# Sheet2.net
KiCad netlist of a schematic drawn in Altium Designer
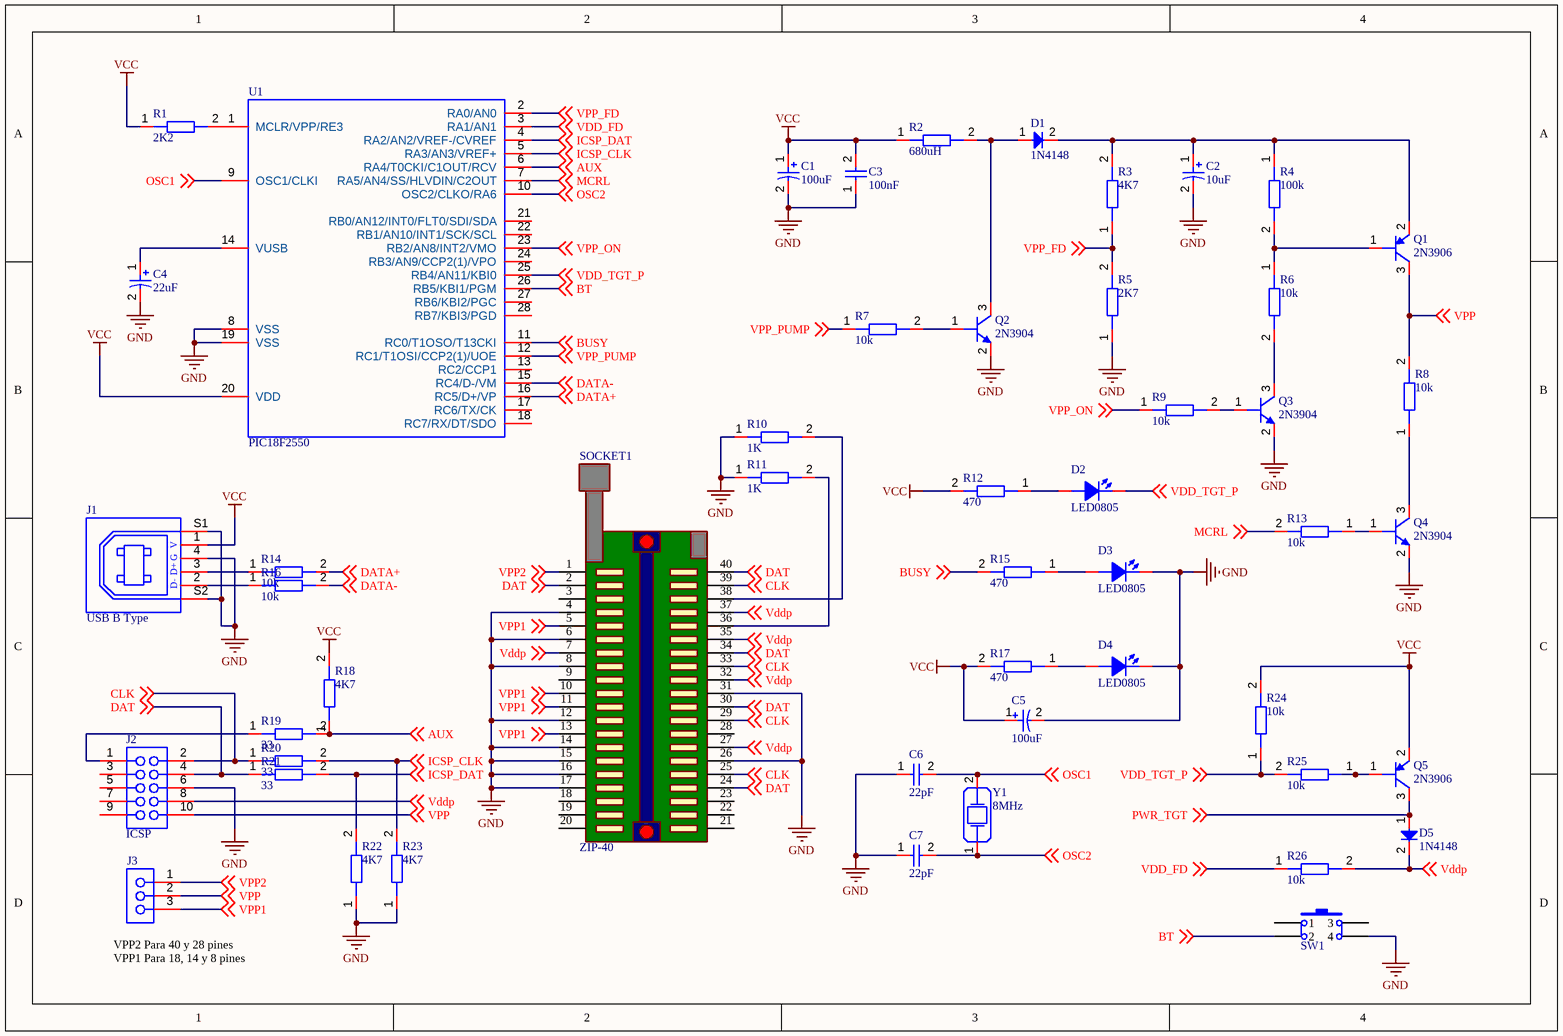
[diagram p0: Sheet2.SchDoc]

(export (version "E")
  (design (tool "Eeschema 10.0.6"))
  (components
    (comp (ref "C1")
      (value "100uF")
      (footprint "CAP_6.3_100uF")
      (libsource (lib "SMDLibrary") (part "Capacitor(Radian)"))
    )
    (comp (ref "C2")
      (value "10uF")
      (footprint "CAP_6.3_100uF")
      (libsource (lib "SMDLibrary") (part "Capacitor(Radian)"))
    )
    (comp (ref "C3")
      (value "100nF")
      (footprint "C0805")
      (libsource (lib "SMDLibrary") (part "Capacitors(SMD)"))
    )
    (comp (ref "C4")
      (value "22uF")
      (footprint "CAP_6.3_100uF")
      (libsource (lib "SMDLibrary") (part "Capacitor(Radian)"))
    )
    (comp (ref "C5")
      (value "100uF")
      (footprint "CAP_6.3_100uF")
      (libsource (lib "SMDLibrary") (part "Capacitor(Radian)"))
    )
    (comp (ref "C6")
      (value "22pF")
      (footprint "C0805")
      (libsource (lib "SMDLibrary") (part "Capacitors(SMD)"))
    )
    (comp (ref "C7")
      (value "22pF")
      (footprint "C0805")
      (libsource (lib "SMDLibrary") (part "Capacitors(SMD)"))
    )
    (comp (ref "D1")
      (value "1N4148")
      (footprint "DO-213AB")
      (libsource (lib "SMDLibrary") (part "Diode 1N4148 SMD"))
    )
    (comp (ref "D2") (value "LED0805") (footprint "L0805RED") (libsource (lib "SMDLibrary") (part "LED0805")))
    (comp (ref "D3") (value "LED0805") (footprint "L0805RED") (libsource (lib "SMDLibrary") (part "LED0805")))
    (comp (ref "D4") (value "LED0805") (footprint "L0805RED") (libsource (lib "SMDLibrary") (part "LED0805")))
    (comp (ref "D5")
      (value "1N4148")
      (footprint "DO-213AB")
      (libsource (lib "SMDLibrary") (part "Diode 1N4148 SMD"))
    )
    (comp (ref "J1")
      (value "USB B Type")
      (footprint "USB-B-TYPE")
      (libsource (lib "SMDLibrary") (part "USB B Type"))
    )
    (comp (ref "J2")
      (value "ICSP")
      (footprint "IDC_CONNECTOR_10x2.54")
      (libsource (lib "SMDLibrary") (part "IDC_CONNECTOR_5x2"))
    )
    (comp (ref "J3")
      (value "Header 3x1 TH Pitch 2.54mm")
      (footprint "Header 3x1 TH Pitch 2.54mm")
      (libsource (lib "SMDLibrary") (part "Header 3x1 TH Pitch 2.54mm"))
    )
    (comp (ref "Q1") (value "2N3906") (footprint "SOT23-3") (libsource (lib "SMDLibrary") (part "2N3906")))
    (comp (ref "Q2") (value "2N3904") (footprint "SOT23-3") (libsource (lib "SMDLibrary") (part "2N3904")))
    (comp (ref "Q3") (value "2N3904") (footprint "SOT23-3") (libsource (lib "SMDLibrary") (part "2N3904")))
    (comp (ref "Q4") (value "2N3904") (footprint "SOT23-3") (libsource (lib "SMDLibrary") (part "2N3904")))
    (comp (ref "Q5") (value "2N3906") (footprint "SOT23-3") (libsource (lib "SMDLibrary") (part "2N3906")))
    (comp (ref "R1") (value "2K2") (footprint "R0805") (libsource (lib "") (part "Resistor SMD_1")))
    (comp (ref "R2")
      (value "680uH")
      (footprint "RES-0.5W-HH-MO")
      (libsource (lib "SMDLibrary") (part "Resistors THD"))
    )
    (comp (ref "R3") (value "4K7") (footprint "R0805") (libsource (lib "") (part "Resistor SMD_3")))
    (comp (ref "R4") (value "100k") (footprint "R0805") (libsource (lib "") (part "Resistor SMD_2")))
    (comp (ref "R5") (value "2K7") (footprint "R0805") (libsource (lib "") (part "Resistor SMD_3")))
    (comp (ref "R6") (value "10k") (footprint "R0805") (libsource (lib "") (part "Resistor SMD_2")))
    (comp (ref "R7") (value "10k") (footprint "R0805") (libsource (lib "") (part "Resistor SMD_1")))
    (comp (ref "R8") (value "10k") (footprint "R0805") (libsource (lib "") (part "Resistor SMD_3")))
    (comp (ref "R9") (value "10k") (footprint "R0805") (libsource (lib "") (part "Resistor SMD_1")))
    (comp (ref "R10") (value "1K") (footprint "R0805") (libsource (lib "") (part "Resistor SMD_1")))
    (comp (ref "R11") (value "1K") (footprint "R0805") (libsource (lib "") (part "Resistor SMD_1")))
    (comp (ref "R12") (value "470") (footprint "R0805") (libsource (lib "SMDLibrary") (part "Resistor SMD")))
    (comp (ref "R13") (value "10k") (footprint "R0805") (libsource (lib "SMDLibrary") (part "Resistor SMD")))
    (comp (ref "R14") (value "10k") (footprint "R0805") (libsource (lib "") (part "Resistor SMD_1")))
    (comp (ref "R15") (value "470") (footprint "R0805") (libsource (lib "SMDLibrary") (part "Resistor SMD")))
    (comp (ref "R16") (value "10k") (footprint "R0805") (libsource (lib "") (part "Resistor SMD_1")))
    (comp (ref "R17") (value "470") (footprint "R0805") (libsource (lib "SMDLibrary") (part "Resistor SMD")))
    (comp (ref "R18") (value "4K7") (footprint "R0805") (libsource (lib "") (part "Resistor SMD_3")))
    (comp (ref "R19") (value "33") (footprint "R0805") (libsource (lib "") (part "Resistor SMD_1")))
    (comp (ref "R20") (value "33") (footprint "R0805") (libsource (lib "") (part "Resistor SMD_1")))
    (comp (ref "R21") (value "33") (footprint "R0805") (libsource (lib "") (part "Resistor SMD_1")))
    (comp (ref "R22") (value "4K7") (footprint "R0805") (libsource (lib "") (part "Resistor SMD_3")))
    (comp (ref "R23") (value "4K7") (footprint "R0805") (libsource (lib "") (part "Resistor SMD_3")))
    (comp (ref "R24") (value "10k") (footprint "R0805") (libsource (lib "") (part "Resistor SMD_3")))
    (comp (ref "R25") (value "10k") (footprint "R0805") (libsource (lib "SMDLibrary") (part "Resistor SMD")))
    (comp (ref "R26") (value "10k") (footprint "R0805") (libsource (lib "") (part "Resistor SMD_1")))
    (comp (ref "SOCKET1")
      (value "ZIP-40")
      (footprint "ZIP-40")
      (libsource (lib "SMDLibrary") (part "ZIP-40"))
    )
    (comp (ref "SW1")
      (value "Button1")
      (footprint "BUTTON_HOLE_4.3mm")
      (libsource (lib "SMDLibrary") (part "Button1"))
    )
    (comp (ref "U1")
      (value "PIC18F2550")
      (footprint "DIP28_M04")
      (libsource (lib "SMDLibrary") (part "PIC18F2550"))
    )
    (comp (ref "Y1")
      (value "8MHz")
      (footprint "HC-49_THROUGH")
      (libsource (lib "SMDLibrary") (part "Crystal"))
    )
  )
  (nets
    (net (code "1") (name "AUX") (class "Default")
      (node (ref "R18") (pin "1") (pinfunction "1_1") (pintype "passive"))
      (node (ref "R19") (pin "2") (pinfunction "2_2") (pintype "passive"))
      (node (ref "U1") (pin "6") (pinfunction "RA4/T0CKI/C1OUT/RCV_6") (pintype "passive"))
    )
    (net (code "2") (name "BT") (class "Default")
      (node (ref "SW1") (pin "2") (pinfunction "2_2") (pintype "passive"))
      (node (ref "U1") (pin "26") (pinfunction "RB5/KBI1/PGM_26") (pintype "passive"))
    )
    (net (code "3") (name "BUSY") (class "Default")
      (node (ref "R15") (pin "2") (pinfunction "2_2") (pintype "passive"))
      (node (ref "U1") (pin "11") (pinfunction "RC0/T1OSO/T13CKI_11") (pintype "passive"))
    )
    (net (code "4") (name "CLK") (class "Default")
      (node (ref "J2") (pin "2") (pinfunction "2_2") (pintype "passive"))
      (node (ref "R20") (pin "1") (pinfunction "1_1") (pintype "passive"))
      (node (ref "SOCKET1") (pin "25") (pinfunction "25_25") (pintype "passive"))
      (node (ref "SOCKET1") (pin "29") (pinfunction "29_29") (pintype "passive"))
      (node (ref "SOCKET1") (pin "33") (pinfunction "33_33") (pintype "passive"))
      (node (ref "SOCKET1") (pin "39") (pinfunction "39_39") (pintype "passive"))
    )
    (net (code "5") (name "DAT") (class "Default")
      (node (ref "J2") (pin "4") (pinfunction "4_4") (pintype "passive"))
      (node (ref "R21") (pin "1") (pinfunction "1_1") (pintype "passive"))
      (node (ref "SOCKET1") (pin "2") (pinfunction "2_2") (pintype "passive"))
      (node (ref "SOCKET1") (pin "24") (pinfunction "24_24") (pintype "passive"))
      (node (ref "SOCKET1") (pin "30") (pinfunction "30_30") (pintype "passive"))
      (node (ref "SOCKET1") (pin "34") (pinfunction "34_34") (pintype "passive"))
      (node (ref "SOCKET1") (pin "40") (pinfunction "40_40") (pintype "passive"))
    )
    (net (code "6") (name "DATA+") (class "Default")
      (node (ref "R14") (pin "2") (pinfunction "2_2") (pintype "passive"))
      (node (ref "U1") (pin "16") (pinfunction "RC5/D+/VP_16") (pintype "passive"))
    )
    (net (code "7") (name "DATA-") (class "Default")
      (node (ref "R16") (pin "2") (pinfunction "2_2") (pintype "passive"))
      (node (ref "U1") (pin "15") (pinfunction "RC4/D-/VM_15") (pintype "passive"))
    )
    (net (code "8") (name "GND") (class "Default")
      (node (ref "C1") (pin "2") (pinfunction "2_2") (pintype "passive"))
      (node (ref "C2") (pin "2") (pinfunction "2_2") (pintype "passive"))
      (node (ref "C3") (pin "1") (pinfunction "1_1") (pintype "passive"))
      (node (ref "C4") (pin "2") (pinfunction "2_2") (pintype "passive"))
      (node (ref "C5") (pin "2") (pinfunction "2_2") (pintype "passive"))
      (node (ref "C6") (pin "1") (pinfunction "1_1") (pintype "passive"))
      (node (ref "C7") (pin "1") (pinfunction "1_1") (pintype "passive"))
      (node (ref "D3") (pin "2") (pinfunction "K_2") (pintype "passive"))
      (node (ref "D4") (pin "2") (pinfunction "K_2") (pintype "passive"))
      (node (ref "J1") (pin "4") (pinfunction "4_4") (pintype "passive"))
      (node (ref "J1") (pin "S1") (pinfunction "S1_S1") (pintype "passive"))
      (node (ref "J1") (pin "S2") (pinfunction "S2_S2") (pintype "passive"))
      (node (ref "J2") (pin "6") (pinfunction "6_6") (pintype "passive"))
      (node (ref "Q2") (pin "2") (pinfunction "E_2") (pintype "passive"))
      (node (ref "Q3") (pin "2") (pinfunction "E_2") (pintype "passive"))
      (node (ref "Q4") (pin "2") (pinfunction "E_2") (pintype "passive"))
      (node (ref "R10") (pin "1") (pinfunction "1_1") (pintype "passive"))
      (node (ref "R11") (pin "1") (pinfunction "1_1") (pintype "passive"))
      (node (ref "R22") (pin "1") (pinfunction "1_1") (pintype "passive"))
      (node (ref "R23") (pin "1") (pinfunction "1_1") (pintype "passive"))
      (node (ref "R5") (pin "1") (pinfunction "1_1") (pintype "passive"))
      (node (ref "SOCKET1") (pin "12") (pinfunction "12_12") (pintype "passive"))
      (node (ref "SOCKET1") (pin "14") (pinfunction "14_14") (pintype "passive"))
      (node (ref "SOCKET1") (pin "15") (pinfunction "15_15") (pintype "passive"))
      (node (ref "SOCKET1") (pin "16") (pinfunction "16_16") (pintype "passive"))
      (node (ref "SOCKET1") (pin "17") (pinfunction "17_17") (pintype "passive"))
      (node (ref "SOCKET1") (pin "26") (pinfunction "26_26") (pintype "passive"))
      (node (ref "SOCKET1") (pin "31") (pinfunction "31_31") (pintype "passive"))
      (node (ref "SOCKET1") (pin "4") (pinfunction "4_4") (pintype "passive"))
      (node (ref "SOCKET1") (pin "6") (pinfunction "6_6") (pintype "passive"))
      (node (ref "SOCKET1") (pin "8") (pinfunction "8_8") (pintype "passive"))
      (node (ref "SW1") (pin "4") (pinfunction "4_4") (pintype "passive"))
      (node (ref "U1") (pin "19") (pinfunction "VSS_19") (pintype "passive"))
      (node (ref "U1") (pin "8") (pinfunction "VSS_8") (pintype "passive"))
    )
    (net (code "9") (name "ICSP_CLK") (class "Default")
      (node (ref "R20") (pin "2") (pinfunction "2_2") (pintype "passive"))
      (node (ref "R23") (pin "2") (pinfunction "2_2") (pintype "passive"))
      (node (ref "U1") (pin "5") (pinfunction "RA3/AN3/VREF+_5") (pintype "passive"))
    )
    (net (code "10") (name "ICSP_DAT") (class "Default")
      (node (ref "R21") (pin "2") (pinfunction "2_2") (pintype "passive"))
      (node (ref "R22") (pin "2") (pinfunction "2_2") (pintype "passive"))
      (node (ref "U1") (pin "4") (pinfunction "RA2/AN2/VREF-/CVREF_4") (pintype "passive"))
    )
    (net (code "11") (name "MCRL") (class "Default")
      (node (ref "R13") (pin "2") (pinfunction "2_2") (pintype "passive"))
      (node (ref "U1") (pin "7") (pinfunction "RA5/AN4/SS/HLVDIN/C2OUT_7") (pintype "passive"))
    )
    (net (code "12") (name "Net-(D2-A)") (class "Default")
      (node (ref "D2") (pin "1") (pinfunction "A_1") (pintype "passive"))
      (node (ref "R12") (pin "1") (pinfunction "1_1") (pintype "passive"))
    )
    (net (code "13") (name "Net-(D3-A)") (class "Default")
      (node (ref "D3") (pin "1") (pinfunction "A_1") (pintype "passive"))
      (node (ref "R15") (pin "1") (pinfunction "1_1") (pintype "passive"))
    )
    (net (code "14") (name "Net-(D4-A)") (class "Default")
      (node (ref "D4") (pin "1") (pinfunction "A_1") (pintype "passive"))
      (node (ref "R17") (pin "1") (pinfunction "1_1") (pintype "passive"))
    )
    (net (code "15") (name "Net-(J1-Pad2)") (class "Default")
      (node (ref "J1") (pin "2") (pinfunction "2_2") (pintype "passive"))
      (node (ref "R16") (pin "1") (pinfunction "1_1") (pintype "passive"))
    )
    (net (code "16") (name "Net-(J1-Pad3)") (class "Default")
      (node (ref "J1") (pin "3") (pinfunction "3_3") (pintype "passive"))
      (node (ref "R14") (pin "1") (pinfunction "1_1") (pintype "passive"))
    )
    (net (code "17") (name "Net-(J2-Pad1)") (class "Default")
      (node (ref "J2") (pin "1") (pinfunction "1_1") (pintype "passive"))
      (node (ref "R19") (pin "1") (pinfunction "1_1") (pintype "passive"))
    )
    (net (code "18") (name "Net-(Q1-B)") (class "Default")
      (node (ref "Q1") (pin "1") (pinfunction "B_1") (pintype "passive"))
      (node (ref "R4") (pin "2") (pinfunction "2_2") (pintype "passive"))
      (node (ref "R6") (pin "1") (pinfunction "1_1") (pintype "passive"))
    )
    (net (code "19") (name "Net-(Q1-E)") (class "Default")
      (node (ref "C2") (pin "1") (pinfunction "1_1") (pintype "passive"))
      (node (ref "D1") (pin "2") (pinfunction "2_2") (pintype "passive"))
      (node (ref "Q1") (pin "2") (pinfunction "E_2") (pintype "passive"))
      (node (ref "R3") (pin "2") (pinfunction "2_2") (pintype "passive"))
      (node (ref "R4") (pin "1") (pinfunction "1_1") (pintype "passive"))
    )
    (net (code "20") (name "Net-(Q2-B)") (class "Default")
      (node (ref "Q2") (pin "1") (pinfunction "B_1") (pintype "passive"))
      (node (ref "R7") (pin "2") (pinfunction "2_2") (pintype "passive"))
    )
    (net (code "21") (name "Net-(Q2-C)") (class "Default")
      (node (ref "D1") (pin "1") (pinfunction "1_1") (pintype "passive"))
      (node (ref "Q2") (pin "3") (pinfunction "C_3") (pintype "passive"))
      (node (ref "R2") (pin "2") (pinfunction "2_2") (pintype "passive"))
    )
    (net (code "22") (name "Net-(Q3-B)") (class "Default")
      (node (ref "Q3") (pin "1") (pinfunction "B_1") (pintype "passive"))
      (node (ref "R9") (pin "2") (pinfunction "2_2") (pintype "passive"))
    )
    (net (code "23") (name "Net-(Q3-C)") (class "Default")
      (node (ref "Q3") (pin "3") (pinfunction "C_3") (pintype "passive"))
      (node (ref "R6") (pin "2") (pinfunction "2_2") (pintype "passive"))
    )
    (net (code "24") (name "Net-(Q4-B)") (class "Default")
      (node (ref "Q4") (pin "1") (pinfunction "B_1") (pintype "passive"))
      (node (ref "R13") (pin "1") (pinfunction "1_1") (pintype "passive"))
    )
    (net (code "25") (name "Net-(Q4-C)") (class "Default")
      (node (ref "Q4") (pin "3") (pinfunction "C_3") (pintype "passive"))
      (node (ref "R8") (pin "1") (pinfunction "1_1") (pintype "passive"))
    )
    (net (code "26") (name "Net-(Q5-B)") (class "Default")
      (node (ref "Q5") (pin "1") (pinfunction "B_1") (pintype "passive"))
      (node (ref "R25") (pin "1") (pinfunction "1_1") (pintype "passive"))
    )
    (net (code "27") (name "Net-(R10-Pad2)") (class "Default")
      (node (ref "R10") (pin "2") (pinfunction "2_2") (pintype "passive"))
      (node (ref "SOCKET1") (pin "38") (pinfunction "38_38") (pintype "passive"))
    )
    (net (code "28") (name "Net-(R11-Pad2)") (class "Default")
      (node (ref "R11") (pin "2") (pinfunction "2_2") (pintype "passive"))
      (node (ref "SOCKET1") (pin "36") (pinfunction "36_36") (pintype "passive"))
    )
    (net (code "29") (name "Net-(U1-MCLR{slash}VPP{slash}RE3)") (class "Default")
      (node (ref "R1") (pin "2") (pinfunction "2_2") (pintype "passive"))
      (node (ref "U1") (pin "1") (pinfunction "MCLR/VPP/RE3_1") (pintype "passive"))
    )
    (net (code "30") (name "Net-(U1-VUSB)") (class "Default")
      (node (ref "C4") (pin "1") (pinfunction "1_1") (pintype "passive"))
      (node (ref "U1") (pin "14") (pinfunction "VUSB_14") (pintype "passive"))
    )
    (net (code "31") (name "OSC1") (class "Default")
      (node (ref "C6") (pin "2") (pinfunction "2_2") (pintype "passive"))
      (node (ref "U1") (pin "9") (pinfunction "OSC1/CLKI_9") (pintype "passive"))
      (node (ref "Y1") (pin "2") (pinfunction "2_2") (pintype "passive"))
    )
    (net (code "32") (name "OSC2") (class "Default")
      (node (ref "C7") (pin "2") (pinfunction "2_2") (pintype "passive"))
      (node (ref "U1") (pin "10") (pinfunction "OSC2/CLKO/RA6_10") (pintype "passive"))
      (node (ref "Y1") (pin "1") (pinfunction "1_1") (pintype "passive"))
    )
    (net (code "33") (name "PWR_TGT") (class "Default")
      (node (ref "D5") (pin "1") (pinfunction "1_1") (pintype "passive"))
      (node (ref "Q5") (pin "3") (pinfunction "C_3") (pintype "passive"))
    )
    (net (code "34") (name "VCC") (class "Default")
      (node (ref "C1") (pin "1") (pinfunction "1_1") (pintype "passive"))
      (node (ref "C3") (pin "2") (pinfunction "2_2") (pintype "passive"))
      (node (ref "C5") (pin "1") (pinfunction "1_1") (pintype "passive"))
      (node (ref "J1") (pin "1") (pinfunction "1_1") (pintype "passive"))
      (node (ref "Q5") (pin "2") (pinfunction "E_2") (pintype "passive"))
      (node (ref "R1") (pin "1") (pinfunction "1_1") (pintype "passive"))
      (node (ref "R12") (pin "2") (pinfunction "2_2") (pintype "passive"))
      (node (ref "R17") (pin "2") (pinfunction "2_2") (pintype "passive"))
      (node (ref "R18") (pin "2") (pinfunction "2_2") (pintype "passive"))
      (node (ref "R2") (pin "1") (pinfunction "1_1") (pintype "passive"))
      (node (ref "R24") (pin "2") (pinfunction "2_2") (pintype "passive"))
      (node (ref "U1") (pin "20") (pinfunction "VDD_20") (pintype "passive"))
    )
    (net (code "35") (name "VDD_FD") (class "Default")
      (node (ref "R26") (pin "1") (pinfunction "1_1") (pintype "passive"))
      (node (ref "U1") (pin "3") (pinfunction "RA1/AN1_3") (pintype "passive"))
    )
    (net (code "36") (name "VDD_TGT_P") (class "Default")
      (node (ref "D2") (pin "2") (pinfunction "K_2") (pintype "passive"))
      (node (ref "R24") (pin "1") (pinfunction "1_1") (pintype "passive"))
      (node (ref "R25") (pin "2") (pinfunction "2_2") (pintype "passive"))
      (node (ref "U1") (pin "25") (pinfunction "RB4/AN11/KBI0_25") (pintype "passive"))
    )
    (net (code "37") (name "VPP") (class "Default")
      (node (ref "J2") (pin "10") (pinfunction "10_10") (pintype "passive"))
      (node (ref "J3") (pin "2") (pinfunction "2_2") (pintype "passive"))
      (node (ref "Q1") (pin "3") (pinfunction "C_3") (pintype "passive"))
      (node (ref "R8") (pin "2") (pinfunction "2_2") (pintype "passive"))
    )
    (net (code "38") (name "VPP1") (class "Default")
      (node (ref "J3") (pin "3") (pinfunction "3_3") (pintype "passive"))
      (node (ref "SOCKET1") (pin "10") (pinfunction "10_10") (pintype "passive"))
      (node (ref "SOCKET1") (pin "11") (pinfunction "11_11") (pintype "passive"))
      (node (ref "SOCKET1") (pin "13") (pinfunction "13_13") (pintype "passive"))
      (node (ref "SOCKET1") (pin "5") (pinfunction "5_5") (pintype "passive"))
    )
    (net (code "39") (name "VPP2") (class "Default")
      (node (ref "J3") (pin "1") (pinfunction "1_1") (pintype "passive"))
      (node (ref "SOCKET1") (pin "1") (pinfunction "1_1") (pintype "passive"))
    )
    (net (code "40") (name "VPP_FD") (class "Default")
      (node (ref "R3") (pin "1") (pinfunction "1_1") (pintype "passive"))
      (node (ref "R5") (pin "2") (pinfunction "2_2") (pintype "passive"))
      (node (ref "U1") (pin "2") (pinfunction "RA0/AN0_2") (pintype "passive"))
    )
    (net (code "41") (name "VPP_ON") (class "Default")
      (node (ref "R9") (pin "1") (pinfunction "1_1") (pintype "passive"))
      (node (ref "U1") (pin "23") (pinfunction "RB2/AN8/INT2/VMO_23") (pintype "passive"))
    )
    (net (code "42") (name "VPP_PUMP") (class "Default")
      (node (ref "R7") (pin "1") (pinfunction "1_1") (pintype "passive"))
      (node (ref "U1") (pin "12") (pinfunction "RC1/T1OSI/CCP2(1)/UOE_12") (pintype "passive"))
    )
    (net (code "43") (name "Vddp") (class "Default")
      (node (ref "D5") (pin "2") (pinfunction "2_2") (pintype "passive"))
      (node (ref "J2") (pin "8") (pinfunction "8_8") (pintype "passive"))
      (node (ref "R26") (pin "2") (pinfunction "2_2") (pintype "passive"))
      (node (ref "SOCKET1") (pin "27") (pinfunction "27_27") (pintype "passive"))
      (node (ref "SOCKET1") (pin "32") (pinfunction "32_32") (pintype "passive"))
      (node (ref "SOCKET1") (pin "35") (pinfunction "35_35") (pintype "passive"))
      (node (ref "SOCKET1") (pin "37") (pinfunction "37_37") (pintype "passive"))
      (node (ref "SOCKET1") (pin "7") (pinfunction "7_7") (pintype "passive"))
    )
    (net (code "44") (name "unconnected-(J2-Pad3)") (class "Default")
      (node (ref "J2") (pin "3") (pinfunction "3_3") (pintype "passive"))
    )
    (net (code "45") (name "unconnected-(J2-Pad5)") (class "Default")
      (node (ref "J2") (pin "5") (pinfunction "5_5") (pintype "passive"))
    )
    (net (code "46") (name "unconnected-(J2-Pad7)") (class "Default")
      (node (ref "J2") (pin "7") (pinfunction "7_7") (pintype "passive"))
    )
    (net (code "47") (name "unconnected-(J2-Pad9)") (class "Default")
      (node (ref "J2") (pin "9") (pinfunction "9_9") (pintype "passive"))
    )
    (net (code "48") (name "unconnected-(SOCKET1-Pad3)") (class "Default")
      (node (ref "SOCKET1") (pin "3") (pinfunction "3_3") (pintype "passive"))
    )
    (net (code "49") (name "unconnected-(SOCKET1-Pad9)") (class "Default")
      (node (ref "SOCKET1") (pin "9") (pinfunction "9_9") (pintype "passive"))
    )
    (net (code "50") (name "unconnected-(SOCKET1-Pad18)") (class "Default")
      (node (ref "SOCKET1") (pin "18") (pinfunction "18_18") (pintype "passive"))
    )
    (net (code "51") (name "unconnected-(SOCKET1-Pad19)") (class "Default")
      (node (ref "SOCKET1") (pin "19") (pinfunction "19_19") (pintype "passive"))
    )
    (net (code "52") (name "unconnected-(SOCKET1-Pad20)") (class "Default")
      (node (ref "SOCKET1") (pin "20") (pinfunction "20_20") (pintype "passive"))
    )
    (net (code "53") (name "unconnected-(SOCKET1-Pad21)") (class "Default")
      (node (ref "SOCKET1") (pin "21") (pinfunction "21_21") (pintype "passive"))
    )
    (net (code "54") (name "unconnected-(SOCKET1-Pad22)") (class "Default")
      (node (ref "SOCKET1") (pin "22") (pinfunction "22_22") (pintype "passive"))
    )
    (net (code "55") (name "unconnected-(SOCKET1-Pad23)") (class "Default")
      (node (ref "SOCKET1") (pin "23") (pinfunction "23_23") (pintype "passive"))
    )
    (net (code "56") (name "unconnected-(SOCKET1-Pad28)") (class "Default")
      (node (ref "SOCKET1") (pin "28") (pinfunction "28_28") (pintype "passive"))
    )
    (net (code "57") (name "unconnected-(SW1-Pad1)") (class "Default")
      (node (ref "SW1") (pin "1") (pinfunction "1_1") (pintype "passive"))
    )
    (net (code "58") (name "unconnected-(SW1-Pad3)") (class "Default")
      (node (ref "SW1") (pin "3") (pinfunction "3_3") (pintype "passive"))
    )
    (net (code "59") (name "unconnected-(U1-RB0{slash}AN12{slash}INT0{slash}FLT0{slash}SDI{slash}SDA-Pad21)") (class "Default")
      (node (ref "U1") (pin "21") (pinfunction "RB0/AN12/INT0/FLT0/SDI/SDA_21") (pintype "passive"))
    )
    (net (code "60") (name "unconnected-(U1-RB1{slash}AN10{slash}INT1{slash}SCK{slash}SCL-Pad22)") (class "Default")
      (node (ref "U1") (pin "22") (pinfunction "RB1/AN10/INT1/SCK/SCL_22") (pintype "passive"))
    )
    (net (code "61") (name "unconnected-(U1-RB3{slash}AN9{slash}CCP2(1){slash}VPO-Pad24)") (class "Default")
      (node (ref "U1") (pin "24") (pinfunction "RB3/AN9/CCP2(1)/VPO_24") (pintype "passive"))
    )
    (net (code "62") (name "unconnected-(U1-RB6{slash}KBI2{slash}PGC-Pad27)") (class "Default")
      (node (ref "U1") (pin "27") (pinfunction "RB6/KBI2/PGC_27") (pintype "passive"))
    )
    (net (code "63") (name "unconnected-(U1-RB7{slash}KBI3{slash}PGD-Pad28)") (class "Default")
      (node (ref "U1") (pin "28") (pinfunction "RB7/KBI3/PGD_28") (pintype "passive"))
    )
    (net (code "64") (name "unconnected-(U1-RC2{slash}CCP1-Pad13)") (class "Default")
      (node (ref "U1") (pin "13") (pinfunction "RC2/CCP1_13") (pintype "passive"))
    )
    (net (code "65") (name "unconnected-(U1-RC6{slash}TX{slash}CK-Pad17)") (class "Default")
      (node (ref "U1") (pin "17") (pinfunction "RC6/TX/CK_17") (pintype "passive"))
    )
    (net (code "66") (name "unconnected-(U1-RC7{slash}RX{slash}DT{slash}SDO-Pad18)") (class "Default")
      (node (ref "U1") (pin "18") (pinfunction "RC7/RX/DT/SDO_18") (pintype "passive"))
    )
  )
)
